# AVR_KBD.net
KiCad netlist of a schematic drawn in Altium Designer
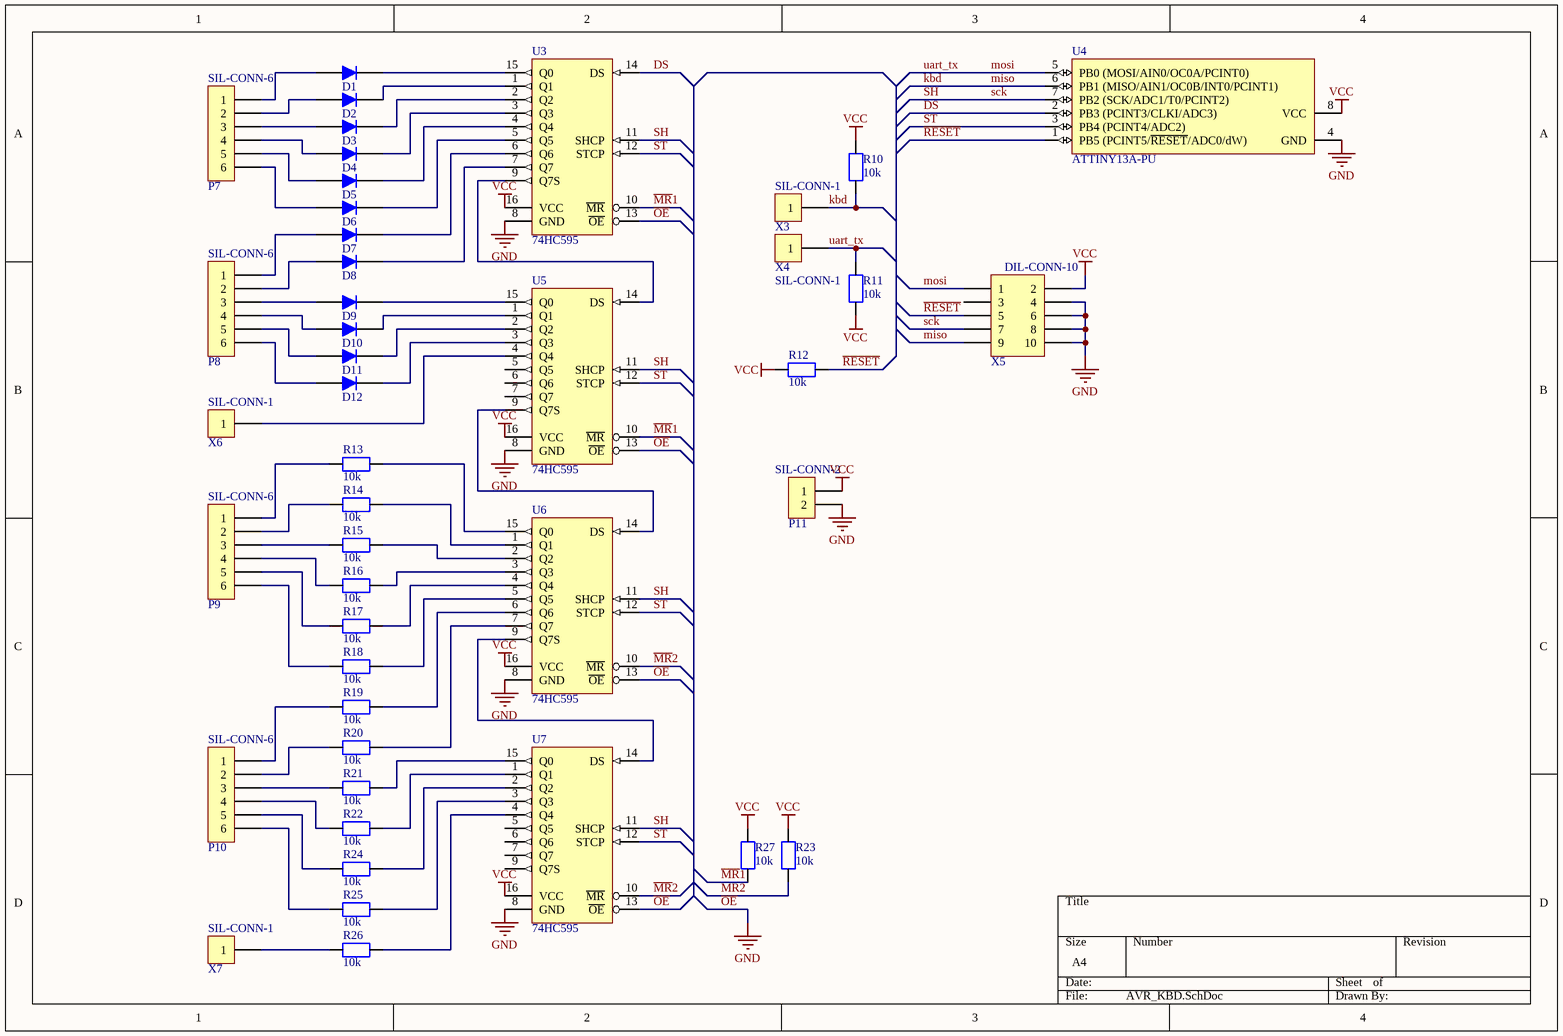
[diagram p0: AVR_KBD.SchDoc]

(export (version "E")
  (design (tool "Eeschema 10.0.6"))
  (components
    (comp (ref "D1") (value "Diode") (footprint "DO35") (libsource (lib "SchLib1") (part "Diode")))
    (comp (ref "D2") (value "Diode") (footprint "DO35") (libsource (lib "SchLib1") (part "Diode")))
    (comp (ref "D3") (value "Diode") (footprint "DO35") (libsource (lib "SchLib1") (part "Diode")))
    (comp (ref "D4") (value "Diode") (footprint "DO35") (libsource (lib "SchLib1") (part "Diode")))
    (comp (ref "D5") (value "Diode") (footprint "DO35") (libsource (lib "SchLib1") (part "Diode")))
    (comp (ref "D6") (value "Diode") (footprint "DO35") (libsource (lib "SchLib1") (part "Diode")))
    (comp (ref "D7") (value "Diode") (footprint "DO35") (libsource (lib "SchLib1") (part "Diode")))
    (comp (ref "D8") (value "Diode") (footprint "DO35") (libsource (lib "SchLib1") (part "Diode")))
    (comp (ref "D9") (value "Diode") (footprint "DO35") (libsource (lib "SchLib1") (part "Diode")))
    (comp (ref "D10") (value "Diode") (footprint "DO35") (libsource (lib "SchLib1") (part "Diode")))
    (comp (ref "D11") (value "Diode") (footprint "DO35") (libsource (lib "SchLib1") (part "Diode")))
    (comp (ref "D12") (value "Diode") (footprint "DO35") (libsource (lib "SchLib1") (part "Diode")))
    (comp (ref "P7")
      (value "SIL-CONN-6")
      (footprint "SIL-CONN-6")
      (libsource (lib "SchLib1") (part "SIL-CONN-6"))
    )
    (comp (ref "P8")
      (value "SIL-CONN-6")
      (footprint "SIL-CONN-6")
      (libsource (lib "SchLib1") (part "SIL-CONN-6"))
    )
    (comp (ref "P9")
      (value "SIL-CONN-6")
      (footprint "SIL-CONN-6")
      (libsource (lib "SchLib1") (part "SIL-CONN-6"))
    )
    (comp (ref "P10")
      (value "SIL-CONN-6")
      (footprint "SIL-CONN-6")
      (libsource (lib "SchLib1") (part "SIL-CONN-6"))
    )
    (comp (ref "P11")
      (value "SIL-CONN-2")
      (footprint "SIL-CONN-2")
      (libsource (lib "SchLib1") (part "SIL-CONN-2"))
    )
    (comp (ref "R10")
      (value "10k")
      (footprint "0805_Resistor")
      (fields (field (name "Comment") "Resistor"))
      (libsource (lib "") (part "Resistor_1"))
    )
    (comp (ref "R11")
      (value "10k")
      (footprint "0805_Resistor")
      (fields (field (name "Comment") "Resistor"))
      (libsource (lib "") (part "Resistor_1"))
    )
    (comp (ref "R12")
      (value "10k")
      (footprint "0805_Resistor")
      (fields (field (name "Comment") "Resistor"))
      (libsource (lib "") (part "Resistor_2"))
    )
    (comp (ref "R13")
      (value "10k")
      (footprint "0805_Resistor")
      (fields (field (name "Comment") "Resistor"))
      (libsource (lib "SchLib1") (part "Resistor"))
    )
    (comp (ref "R14")
      (value "10k")
      (footprint "0805_Resistor")
      (fields (field (name "Comment") "Resistor"))
      (libsource (lib "SchLib1") (part "Resistor"))
    )
    (comp (ref "R15")
      (value "10k")
      (footprint "0805_Resistor")
      (fields (field (name "Comment") "Resistor"))
      (libsource (lib "SchLib1") (part "Resistor"))
    )
    (comp (ref "R16")
      (value "10k")
      (footprint "0805_Resistor")
      (fields (field (name "Comment") "Resistor"))
      (libsource (lib "SchLib1") (part "Resistor"))
    )
    (comp (ref "R17")
      (value "10k")
      (footprint "0805_Resistor")
      (fields (field (name "Comment") "Resistor"))
      (libsource (lib "SchLib1") (part "Resistor"))
    )
    (comp (ref "R18")
      (value "10k")
      (footprint "0805_Resistor")
      (fields (field (name "Comment") "Resistor"))
      (libsource (lib "SchLib1") (part "Resistor"))
    )
    (comp (ref "R19")
      (value "10k")
      (footprint "0805_Resistor")
      (fields (field (name "Comment") "Resistor"))
      (libsource (lib "SchLib1") (part "Resistor"))
    )
    (comp (ref "R20")
      (value "10k")
      (footprint "0805_Resistor")
      (fields (field (name "Comment") "Resistor"))
      (libsource (lib "SchLib1") (part "Resistor"))
    )
    (comp (ref "R21")
      (value "10k")
      (footprint "0805_Resistor")
      (fields (field (name "Comment") "Resistor"))
      (libsource (lib "SchLib1") (part "Resistor"))
    )
    (comp (ref "R22")
      (value "10k")
      (footprint "0805_Resistor")
      (fields (field (name "Comment") "Resistor"))
      (libsource (lib "SchLib1") (part "Resistor"))
    )
    (comp (ref "R23")
      (value "10k")
      (footprint "0805_Resistor")
      (fields (field (name "Comment") "Resistor"))
      (libsource (lib "") (part "Resistor_1"))
    )
    (comp (ref "R24")
      (value "10k")
      (footprint "0805_Resistor")
      (fields (field (name "Comment") "Resistor"))
      (libsource (lib "SchLib1") (part "Resistor"))
    )
    (comp (ref "R25")
      (value "10k")
      (footprint "0805_Resistor")
      (fields (field (name "Comment") "Resistor"))
      (libsource (lib "SchLib1") (part "Resistor"))
    )
    (comp (ref "R26")
      (value "10k")
      (footprint "0805_Resistor")
      (fields (field (name "Comment") "Resistor"))
      (libsource (lib "SchLib1") (part "Resistor"))
    )
    (comp (ref "R27")
      (value "10k")
      (footprint "0805_Resistor")
      (fields (field (name "Comment") "Resistor"))
      (libsource (lib "") (part "Resistor_1"))
    )
    (comp (ref "U3") (value "74HC595") (footprint "SOIC16") (libsource (lib "SchLib1") (part "74HC595")))
    (comp (ref "U4")
      (value "ATTINY13A-PU")
      (footprint "DIP8")
      (libsource (lib "SchLib1") (part "ATTINY13A-PU"))
    )
    (comp (ref "U5") (value "74HC595") (footprint "SOIC16") (libsource (lib "SchLib1") (part "74HC595")))
    (comp (ref "U6") (value "74HC595") (footprint "SOIC16") (libsource (lib "SchLib1") (part "74HC595")))
    (comp (ref "U7") (value "74HC595") (footprint "SOIC16") (libsource (lib "SchLib1") (part "74HC595")))
    (comp (ref "X3")
      (value "SIL-CONN-1")
      (footprint "SIL-CONN-1")
      (libsource (lib "SchLib1") (part "SIL-CONN-1"))
    )
    (comp (ref "X4")
      (value "SIL-CONN-1")
      (footprint "SIL-CONN-1")
      (libsource (lib "SchLib1") (part "SIL-CONN-1"))
    )
    (comp (ref "X5")
      (value "DIL-CONN-10")
      (footprint "DIL-CONN-IDC-10")
      (libsource (lib "SchLib1") (part "DIL-CONN-10"))
    )
    (comp (ref "X6")
      (value "SIL-CONN-1")
      (footprint "SIL-CONN-1")
      (libsource (lib "SchLib1") (part "SIL-CONN-1"))
    )
    (comp (ref "X7")
      (value "SIL-CONN-1")
      (footprint "SIL-CONN-1")
      (libsource (lib "SchLib1") (part "SIL-CONN-1"))
    )
  )
  (nets
    (net (code "1") (name "/DS") (class "Default")
      (node (ref "U3") (pin "14") (pinfunction "DS_14") (pintype "input"))
      (node (ref "U4") (pin "2") (pinfunction "PB3_(PCINT3/CLKI/ADC3)_2") (pintype "bidirectional"))
    )
    (net (code "2") (name "/SH") (class "Default")
      (node (ref "U3") (pin "11") (pinfunction "SHCP_11") (pintype "input"))
      (node (ref "U4") (pin "7") (pinfunction "PB2_(SCK/ADC1/T0/PCINT2)_7") (pintype "bidirectional"))
      (node (ref "U5") (pin "11") (pinfunction "SHCP_11") (pintype "input"))
      (node (ref "U6") (pin "11") (pinfunction "SHCP_11") (pintype "input"))
      (node (ref "U7") (pin "11") (pinfunction "SHCP_11") (pintype "input"))
      (node (ref "X5") (pin "7") (pinfunction "7_7") (pintype "passive"))
    )
    (net (code "3") (name "/ST") (class "Default")
      (node (ref "U3") (pin "12") (pinfunction "STCP_12") (pintype "input"))
      (node (ref "U4") (pin "3") (pinfunction "PB4_(PCINT4/ADC2)_3") (pintype "bidirectional"))
      (node (ref "U5") (pin "12") (pinfunction "STCP_12") (pintype "input"))
      (node (ref "U6") (pin "12") (pinfunction "STCP_12") (pintype "input"))
      (node (ref "U7") (pin "12") (pinfunction "STCP_12") (pintype "input"))
    )
    (net (code "4") (name "/kbd") (class "Default")
      (node (ref "R10") (pin "1") (pinfunction "1_1") (pintype "passive"))
      (node (ref "U4") (pin "6") (pinfunction "PB1_(MISO/AIN1/OC0B/INT0/PCINT1)_6") (pintype "bidirectional"))
      (node (ref "X3") (pin "1") (pinfunction "1_1") (pintype "passive"))
      (node (ref "X5") (pin "9") (pinfunction "9_9") (pintype "passive"))
    )
    (net (code "5") (name "/mosi") (class "Default")
      (node (ref "R11") (pin "2") (pinfunction "2_2") (pintype "passive"))
      (node (ref "U4") (pin "5") (pinfunction "PB0_(MOSI/AIN0/OC0A/PCINT0)_5") (pintype "bidirectional"))
      (node (ref "X4") (pin "1") (pinfunction "1_1") (pintype "passive"))
      (node (ref "X5") (pin "1") (pinfunction "1_1") (pintype "passive"))
    )
    (net (code "6") (name "/~{MR}1") (class "Default")
      (node (ref "R27") (pin "1") (pinfunction "1_1") (pintype "passive"))
      (node (ref "U3") (pin "10") (pinfunction "~{MR}_10") (pintype "passive"))
      (node (ref "U5") (pin "10") (pinfunction "~{MR}_10") (pintype "passive"))
    )
    (net (code "7") (name "/~{MR}2") (class "Default")
      (node (ref "R23") (pin "1") (pinfunction "1_1") (pintype "passive"))
      (node (ref "U6") (pin "10") (pinfunction "~{MR}_10") (pintype "passive"))
      (node (ref "U7") (pin "10") (pinfunction "~{MR}_10") (pintype "passive"))
    )
    (net (code "8") (name "/~{RESET}") (class "Default")
      (node (ref "R12") (pin "1") (pinfunction "1_1") (pintype "passive"))
      (node (ref "U4") (pin "1") (pinfunction "PB5_(PCINT5/~{RESET}/ADC0/dW)_1") (pintype "bidirectional"))
      (node (ref "X5") (pin "5") (pinfunction "5_5") (pintype "passive"))
    )
    (net (code "9") (name "GND") (class "Default")
      (node (ref "P11") (pin "2") (pinfunction "2_2") (pintype "passive"))
      (node (ref "U3") (pin "13") (pinfunction "~{OE}_13") (pintype "passive"))
      (node (ref "U3") (pin "8") (pinfunction "GND_8") (pintype "power_in"))
      (node (ref "U4") (pin "4") (pinfunction "GND_4") (pintype "power_in"))
      (node (ref "U5") (pin "13") (pinfunction "~{OE}_13") (pintype "passive"))
      (node (ref "U5") (pin "8") (pinfunction "GND_8") (pintype "power_in"))
      (node (ref "U6") (pin "13") (pinfunction "~{OE}_13") (pintype "passive"))
      (node (ref "U6") (pin "8") (pinfunction "GND_8") (pintype "power_in"))
      (node (ref "U7") (pin "13") (pinfunction "~{OE}_13") (pintype "passive"))
      (node (ref "U7") (pin "8") (pinfunction "GND_8") (pintype "power_in"))
      (node (ref "X5") (pin "10") (pinfunction "10_10") (pintype "passive"))
      (node (ref "X5") (pin "4") (pinfunction "4_4") (pintype "passive"))
      (node (ref "X5") (pin "6") (pinfunction "6_6") (pintype "passive"))
      (node (ref "X5") (pin "8") (pinfunction "8_8") (pintype "passive"))
    )
    (net (code "10") (name "Net-(D1-PadA)") (class "Default")
      (node (ref "D1") (pin "A") (pinfunction "A_A") (pintype "passive"))
      (node (ref "P7") (pin "1") (pinfunction "1_1") (pintype "passive"))
    )
    (net (code "11") (name "Net-(D2-PadA)") (class "Default")
      (node (ref "D2") (pin "A") (pinfunction "A_A") (pintype "passive"))
      (node (ref "P7") (pin "2") (pinfunction "2_2") (pintype "passive"))
    )
    (net (code "12") (name "Net-(D3-PadA)") (class "Default")
      (node (ref "D3") (pin "A") (pinfunction "A_A") (pintype "passive"))
      (node (ref "P7") (pin "3") (pinfunction "3_3") (pintype "passive"))
    )
    (net (code "13") (name "Net-(D4-PadA)") (class "Default")
      (node (ref "D4") (pin "A") (pinfunction "A_A") (pintype "passive"))
      (node (ref "P7") (pin "4") (pinfunction "4_4") (pintype "passive"))
    )
    (net (code "14") (name "Net-(D5-PadA)") (class "Default")
      (node (ref "D5") (pin "A") (pinfunction "A_A") (pintype "passive"))
      (node (ref "P7") (pin "5") (pinfunction "5_5") (pintype "passive"))
    )
    (net (code "15") (name "Net-(D6-PadA)") (class "Default")
      (node (ref "D6") (pin "A") (pinfunction "A_A") (pintype "passive"))
      (node (ref "P7") (pin "6") (pinfunction "6_6") (pintype "passive"))
    )
    (net (code "16") (name "Net-(D7-PadA)") (class "Default")
      (node (ref "D7") (pin "A") (pinfunction "A_A") (pintype "passive"))
      (node (ref "P8") (pin "1") (pinfunction "1_1") (pintype "passive"))
    )
    (net (code "17") (name "Net-(D8-PadA)") (class "Default")
      (node (ref "D8") (pin "A") (pinfunction "A_A") (pintype "passive"))
      (node (ref "P8") (pin "2") (pinfunction "2_2") (pintype "passive"))
    )
    (net (code "18") (name "Net-(D9-PadA)") (class "Default")
      (node (ref "D9") (pin "A") (pinfunction "A_A") (pintype "passive"))
      (node (ref "P8") (pin "3") (pinfunction "3_3") (pintype "passive"))
    )
    (net (code "19") (name "Net-(D10-PadA)") (class "Default")
      (node (ref "D10") (pin "A") (pinfunction "A_A") (pintype "passive"))
      (node (ref "P8") (pin "4") (pinfunction "4_4") (pintype "passive"))
    )
    (net (code "20") (name "Net-(D11-PadA)") (class "Default")
      (node (ref "D11") (pin "A") (pinfunction "A_A") (pintype "passive"))
      (node (ref "P8") (pin "5") (pinfunction "5_5") (pintype "passive"))
    )
    (net (code "21") (name "Net-(D12-PadA)") (class "Default")
      (node (ref "D12") (pin "A") (pinfunction "A_A") (pintype "passive"))
      (node (ref "P8") (pin "6") (pinfunction "6_6") (pintype "passive"))
    )
    (net (code "22") (name "Net-(P9-Pad1)") (class "Default")
      (node (ref "P9") (pin "1") (pinfunction "1_1") (pintype "passive"))
      (node (ref "R13") (pin "1") (pinfunction "1_1") (pintype "passive"))
    )
    (net (code "23") (name "Net-(P9-Pad2)") (class "Default")
      (node (ref "P9") (pin "2") (pinfunction "2_2") (pintype "passive"))
      (node (ref "R14") (pin "1") (pinfunction "1_1") (pintype "passive"))
    )
    (net (code "24") (name "Net-(P9-Pad3)") (class "Default")
      (node (ref "P9") (pin "3") (pinfunction "3_3") (pintype "passive"))
      (node (ref "R15") (pin "1") (pinfunction "1_1") (pintype "passive"))
    )
    (net (code "25") (name "Net-(P9-Pad4)") (class "Default")
      (node (ref "P9") (pin "4") (pinfunction "4_4") (pintype "passive"))
      (node (ref "R16") (pin "1") (pinfunction "1_1") (pintype "passive"))
    )
    (net (code "26") (name "Net-(P9-Pad5)") (class "Default")
      (node (ref "P9") (pin "5") (pinfunction "5_5") (pintype "passive"))
      (node (ref "R17") (pin "1") (pinfunction "1_1") (pintype "passive"))
    )
    (net (code "27") (name "Net-(P9-Pad6)") (class "Default")
      (node (ref "P9") (pin "6") (pinfunction "6_6") (pintype "passive"))
      (node (ref "R18") (pin "1") (pinfunction "1_1") (pintype "passive"))
    )
    (net (code "28") (name "Net-(P10-Pad1)") (class "Default")
      (node (ref "P10") (pin "1") (pinfunction "1_1") (pintype "passive"))
      (node (ref "R19") (pin "1") (pinfunction "1_1") (pintype "passive"))
    )
    (net (code "29") (name "Net-(P10-Pad2)") (class "Default")
      (node (ref "P10") (pin "2") (pinfunction "2_2") (pintype "passive"))
      (node (ref "R20") (pin "1") (pinfunction "1_1") (pintype "passive"))
    )
    (net (code "30") (name "Net-(P10-Pad3)") (class "Default")
      (node (ref "P10") (pin "3") (pinfunction "3_3") (pintype "passive"))
      (node (ref "R21") (pin "1") (pinfunction "1_1") (pintype "passive"))
    )
    (net (code "31") (name "Net-(P10-Pad4)") (class "Default")
      (node (ref "P10") (pin "4") (pinfunction "4_4") (pintype "passive"))
      (node (ref "R22") (pin "1") (pinfunction "1_1") (pintype "passive"))
    )
    (net (code "32") (name "Net-(P10-Pad5)") (class "Default")
      (node (ref "P10") (pin "5") (pinfunction "5_5") (pintype "passive"))
      (node (ref "R24") (pin "1") (pinfunction "1_1") (pintype "passive"))
    )
    (net (code "33") (name "Net-(P10-Pad6)") (class "Default")
      (node (ref "P10") (pin "6") (pinfunction "6_6") (pintype "passive"))
      (node (ref "R25") (pin "1") (pinfunction "1_1") (pintype "passive"))
    )
    (net (code "34") (name "Net-(R26-Pad1)") (class "Default")
      (node (ref "R26") (pin "1") (pinfunction "1_1") (pintype "passive"))
      (node (ref "X7") (pin "1") (pinfunction "1_1") (pintype "passive"))
    )
    (net (code "35") (name "Net-(U3-Q0)") (class "Default")
      (node (ref "D1") (pin "K") (pinfunction "K_K") (pintype "passive"))
      (node (ref "U3") (pin "15") (pinfunction "Q0_15") (pintype "output"))
    )
    (net (code "36") (name "Net-(U3-Q1)") (class "Default")
      (node (ref "D2") (pin "K") (pinfunction "K_K") (pintype "passive"))
      (node (ref "U3") (pin "1") (pinfunction "Q1_1") (pintype "output"))
    )
    (net (code "37") (name "Net-(U3-Q2)") (class "Default")
      (node (ref "D3") (pin "K") (pinfunction "K_K") (pintype "passive"))
      (node (ref "U3") (pin "2") (pinfunction "Q2_2") (pintype "output"))
    )
    (net (code "38") (name "Net-(U3-Q3)") (class "Default")
      (node (ref "D4") (pin "K") (pinfunction "K_K") (pintype "passive"))
      (node (ref "U3") (pin "3") (pinfunction "Q3_3") (pintype "output"))
    )
    (net (code "39") (name "Net-(U3-Q4)") (class "Default")
      (node (ref "D5") (pin "K") (pinfunction "K_K") (pintype "passive"))
      (node (ref "U3") (pin "4") (pinfunction "Q4_4") (pintype "output"))
    )
    (net (code "40") (name "Net-(U3-Q5)") (class "Default")
      (node (ref "D6") (pin "K") (pinfunction "K_K") (pintype "passive"))
      (node (ref "U3") (pin "5") (pinfunction "Q5_5") (pintype "output"))
    )
    (net (code "41") (name "Net-(U3-Q6)") (class "Default")
      (node (ref "D7") (pin "K") (pinfunction "K_K") (pintype "passive"))
      (node (ref "U3") (pin "6") (pinfunction "Q6_6") (pintype "output"))
    )
    (net (code "42") (name "Net-(U3-Q7)") (class "Default")
      (node (ref "D8") (pin "K") (pinfunction "K_K") (pintype "passive"))
      (node (ref "U3") (pin "7") (pinfunction "Q7_7") (pintype "output"))
    )
    (net (code "43") (name "Net-(U3-Q7S)") (class "Default")
      (node (ref "U3") (pin "9") (pinfunction "Q7S_9") (pintype "output"))
      (node (ref "U5") (pin "14") (pinfunction "DS_14") (pintype "input"))
    )
    (net (code "44") (name "Net-(U5-Q0)") (class "Default")
      (node (ref "D9") (pin "K") (pinfunction "K_K") (pintype "passive"))
      (node (ref "U5") (pin "15") (pinfunction "Q0_15") (pintype "output"))
    )
    (net (code "45") (name "Net-(U5-Q1)") (class "Default")
      (node (ref "D10") (pin "K") (pinfunction "K_K") (pintype "passive"))
      (node (ref "U5") (pin "1") (pinfunction "Q1_1") (pintype "output"))
    )
    (net (code "46") (name "Net-(U5-Q2)") (class "Default")
      (node (ref "D11") (pin "K") (pinfunction "K_K") (pintype "passive"))
      (node (ref "U5") (pin "2") (pinfunction "Q2_2") (pintype "output"))
    )
    (net (code "47") (name "Net-(U5-Q3)") (class "Default")
      (node (ref "D12") (pin "K") (pinfunction "K_K") (pintype "passive"))
      (node (ref "U5") (pin "3") (pinfunction "Q3_3") (pintype "output"))
    )
    (net (code "48") (name "Net-(U5-Q4)") (class "Default")
      (node (ref "U5") (pin "4") (pinfunction "Q4_4") (pintype "output"))
      (node (ref "X6") (pin "1") (pinfunction "1_1") (pintype "passive"))
    )
    (net (code "49") (name "Net-(U5-Q7S)") (class "Default")
      (node (ref "U5") (pin "9") (pinfunction "Q7S_9") (pintype "output"))
      (node (ref "U6") (pin "14") (pinfunction "DS_14") (pintype "input"))
    )
    (net (code "50") (name "Net-(U6-Q0)") (class "Default")
      (node (ref "R13") (pin "2") (pinfunction "2_2") (pintype "passive"))
      (node (ref "U6") (pin "15") (pinfunction "Q0_15") (pintype "output"))
    )
    (net (code "51") (name "Net-(U6-Q1)") (class "Default")
      (node (ref "R14") (pin "2") (pinfunction "2_2") (pintype "passive"))
      (node (ref "U6") (pin "1") (pinfunction "Q1_1") (pintype "output"))
    )
    (net (code "52") (name "Net-(U6-Q2)") (class "Default")
      (node (ref "R15") (pin "2") (pinfunction "2_2") (pintype "passive"))
      (node (ref "U6") (pin "2") (pinfunction "Q2_2") (pintype "output"))
    )
    (net (code "53") (name "Net-(U6-Q3)") (class "Default")
      (node (ref "R16") (pin "2") (pinfunction "2_2") (pintype "passive"))
      (node (ref "U6") (pin "3") (pinfunction "Q3_3") (pintype "output"))
    )
    (net (code "54") (name "Net-(U6-Q4)") (class "Default")
      (node (ref "R17") (pin "2") (pinfunction "2_2") (pintype "passive"))
      (node (ref "U6") (pin "4") (pinfunction "Q4_4") (pintype "output"))
    )
    (net (code "55") (name "Net-(U6-Q5)") (class "Default")
      (node (ref "R18") (pin "2") (pinfunction "2_2") (pintype "passive"))
      (node (ref "U6") (pin "5") (pinfunction "Q5_5") (pintype "output"))
    )
    (net (code "56") (name "Net-(U6-Q6)") (class "Default")
      (node (ref "R19") (pin "2") (pinfunction "2_2") (pintype "passive"))
      (node (ref "U6") (pin "6") (pinfunction "Q6_6") (pintype "output"))
    )
    (net (code "57") (name "Net-(U6-Q7)") (class "Default")
      (node (ref "R20") (pin "2") (pinfunction "2_2") (pintype "passive"))
      (node (ref "U6") (pin "7") (pinfunction "Q7_7") (pintype "output"))
    )
    (net (code "58") (name "Net-(U6-Q7S)") (class "Default")
      (node (ref "U6") (pin "9") (pinfunction "Q7S_9") (pintype "output"))
      (node (ref "U7") (pin "14") (pinfunction "DS_14") (pintype "input"))
    )
    (net (code "59") (name "Net-(U7-Q0)") (class "Default")
      (node (ref "R21") (pin "2") (pinfunction "2_2") (pintype "passive"))
      (node (ref "U7") (pin "15") (pinfunction "Q0_15") (pintype "output"))
    )
    (net (code "60") (name "Net-(U7-Q1)") (class "Default")
      (node (ref "R22") (pin "2") (pinfunction "2_2") (pintype "passive"))
      (node (ref "U7") (pin "1") (pinfunction "Q1_1") (pintype "output"))
    )
    (net (code "61") (name "Net-(U7-Q2)") (class "Default")
      (node (ref "R24") (pin "2") (pinfunction "2_2") (pintype "passive"))
      (node (ref "U7") (pin "2") (pinfunction "Q2_2") (pintype "output"))
    )
    (net (code "62") (name "Net-(U7-Q3)") (class "Default")
      (node (ref "R25") (pin "2") (pinfunction "2_2") (pintype "passive"))
      (node (ref "U7") (pin "3") (pinfunction "Q3_3") (pintype "output"))
    )
    (net (code "63") (name "Net-(U7-Q4)") (class "Default")
      (node (ref "R26") (pin "2") (pinfunction "2_2") (pintype "passive"))
      (node (ref "U7") (pin "4") (pinfunction "Q4_4") (pintype "output"))
    )
    (net (code "64") (name "VCC") (class "Default")
      (node (ref "P11") (pin "1") (pinfunction "1_1") (pintype "passive"))
      (node (ref "R10") (pin "2") (pinfunction "2_2") (pintype "passive"))
      (node (ref "R11") (pin "1") (pinfunction "1_1") (pintype "passive"))
      (node (ref "R12") (pin "2") (pinfunction "2_2") (pintype "passive"))
      (node (ref "R23") (pin "2") (pinfunction "2_2") (pintype "passive"))
      (node (ref "R27") (pin "2") (pinfunction "2_2") (pintype "passive"))
      (node (ref "U3") (pin "16") (pinfunction "VCC_16") (pintype "power_in"))
      (node (ref "U4") (pin "8") (pinfunction "VCC_8") (pintype "power_in"))
      (node (ref "U5") (pin "16") (pinfunction "VCC_16") (pintype "power_in"))
      (node (ref "U6") (pin "16") (pinfunction "VCC_16") (pintype "power_in"))
      (node (ref "U7") (pin "16") (pinfunction "VCC_16") (pintype "power_in"))
      (node (ref "X5") (pin "2") (pinfunction "2_2") (pintype "passive"))
    )
    (net (code "65") (name "unconnected-(U5-Q5-Pad5)") (class "Default")
      (node (ref "U5") (pin "5") (pinfunction "Q5_5") (pintype "output"))
    )
    (net (code "66") (name "unconnected-(U5-Q6-Pad6)") (class "Default")
      (node (ref "U5") (pin "6") (pinfunction "Q6_6") (pintype "output"))
    )
    (net (code "67") (name "unconnected-(U5-Q7-Pad7)") (class "Default")
      (node (ref "U5") (pin "7") (pinfunction "Q7_7") (pintype "output"))
    )
    (net (code "68") (name "unconnected-(U7-Q5-Pad5)") (class "Default")
      (node (ref "U7") (pin "5") (pinfunction "Q5_5") (pintype "output"))
    )
    (net (code "69") (name "unconnected-(U7-Q6-Pad6)") (class "Default")
      (node (ref "U7") (pin "6") (pinfunction "Q6_6") (pintype "output"))
    )
    (net (code "70") (name "unconnected-(U7-Q7-Pad7)") (class "Default")
      (node (ref "U7") (pin "7") (pinfunction "Q7_7") (pintype "output"))
    )
    (net (code "71") (name "unconnected-(U7-Q7S-Pad9)") (class "Default")
      (node (ref "U7") (pin "9") (pinfunction "Q7S_9") (pintype "output"))
    )
    (net (code "72") (name "unconnected-(X5-Pad3)") (class "Default")
      (node (ref "X5") (pin "3") (pinfunction "3_3") (pintype "passive"))
    )
  )
)
